# BMS-LV.net
KiCad netlist of a schematic drawn in EAGLE
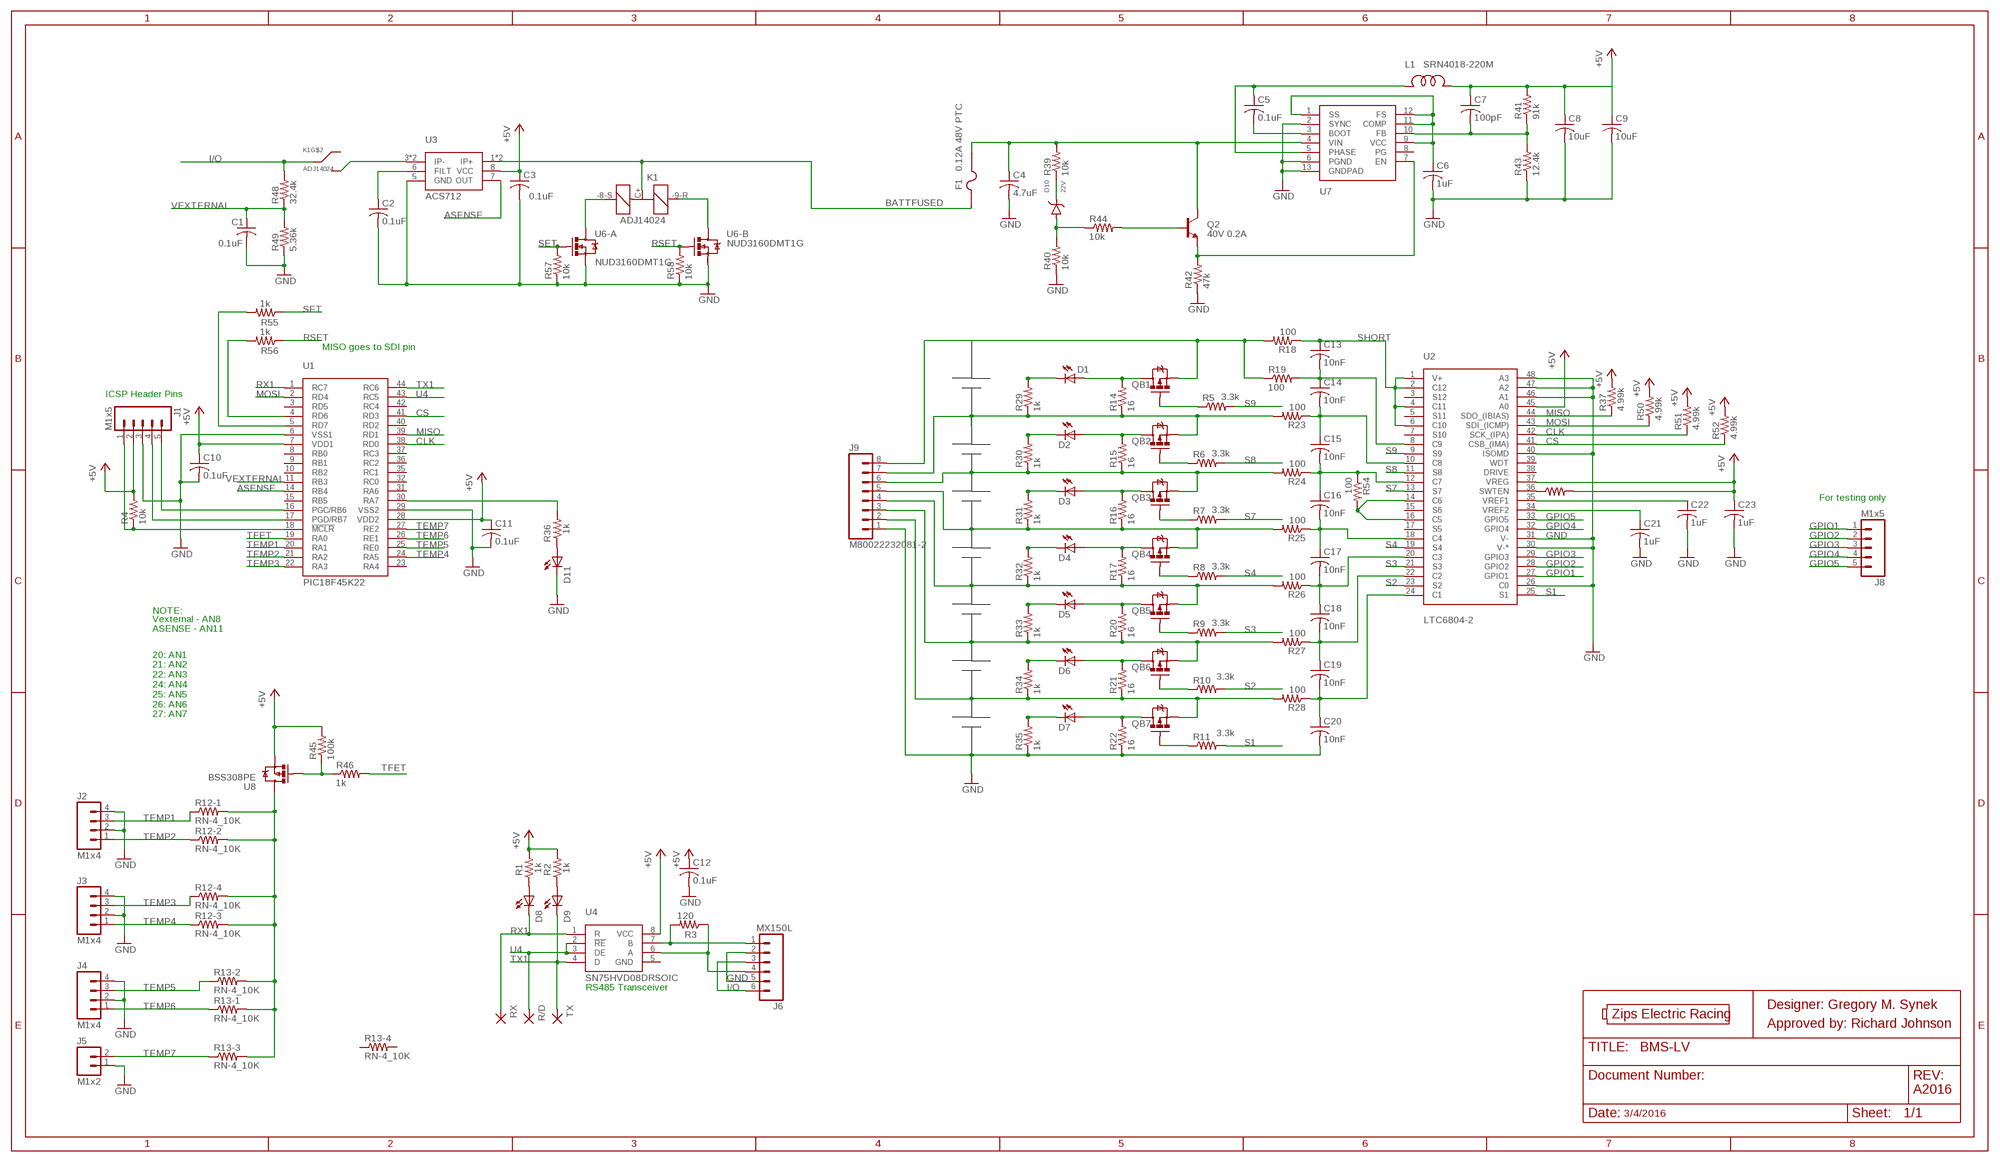
[diagram p0: schematic, sheet 1]

(export (version "E")
  (design (tool "Eeschema 10.0.6"))
  (components
    (comp (ref "C1")
      (value "0.1uF")
      (footprint "eagle-import:0603")
      (fields (field (name "PARTNO") "CC0603ZRY5V9BB104"))
      (libsource (lib "eagle-import") (part "CAP_0.1UF_50V"))
    )
    (comp (ref "C2")
      (value "0.1uF")
      (footprint "eagle-import:0805")
      (fields (field (name "PARTNO") "CL21B104KCC5PNC"))
      (libsource (lib "eagle-import") (part "CAP_0.1UF_100V"))
    )
    (comp (ref "C3")
      (value "0.1uF")
      (footprint "eagle-import:0603")
      (fields (field (name "PARTNO") "CC0603ZRY5V9BB104"))
      (libsource (lib "eagle-import") (part "CAP_0.1UF_50V"))
    )
    (comp (ref "C4")
      (value "4.7uF")
      (footprint "eagle-import:1206@1")
      (fields (field (name "PARTNO") "GRM31CF51H475ZA01L"))
      (libsource (lib "eagle-import") (part "CAP_4.7UF_50V"))
    )
    (comp (ref "C5")
      (value "0.1uF")
      (footprint "eagle-import:0603")
      (fields (field (name "PARTNO") "CC0603ZRY5V9BB104"))
      (libsource (lib "eagle-import") (part "CAP_0.1UF_50V"))
    )
    (comp (ref "C6")
      (value "1uF")
      (footprint "eagle-import:0805")
      (fields (field (name "PARTNO") "UMK212F105ZG-T"))
      (libsource (lib "eagle-import") (part "CAP_1UF_50V_0805"))
    )
    (comp (ref "C7")
      (value "100pF")
      (footprint "eagle-import:0603")
      (fields (field (name "PARTNO") "C1608C0G1H101J080AA"))
      (libsource (lib "eagle-import") (part "CAP_100PF_50V"))
    )
    (comp (ref "C8")
      (value "10uF")
      (footprint "eagle-import:1206@1")
      (fields (field (name "PARTNO") "CL31A106KBHNNNE"))
      (libsource (lib "eagle-import") (part "CAP_10UF_50V"))
    )
    (comp (ref "C9")
      (value "10uF")
      (footprint "eagle-import:1206@1")
      (fields (field (name "PARTNO") "CL31A106KBHNNNE"))
      (libsource (lib "eagle-import") (part "CAP_10UF_50V"))
    )
    (comp (ref "C10")
      (value "0.1uF")
      (footprint "eagle-import:0603")
      (fields (field (name "PARTNO") "CC0603ZRY5V9BB104"))
      (libsource (lib "eagle-import") (part "CAP_0.1UF_50V"))
    )
    (comp (ref "C11")
      (value "0.1uF")
      (footprint "eagle-import:0603")
      (fields (field (name "PARTNO") "CC0603ZRY5V9BB104"))
      (libsource (lib "eagle-import") (part "CAP_0.1UF_50V"))
    )
    (comp (ref "C12")
      (value "0.1uF")
      (footprint "eagle-import:0603")
      (fields (field (name "PARTNO") "CC0603ZRY5V9BB104"))
      (libsource (lib "eagle-import") (part "CAP_0.1UF_50V"))
    )
    (comp (ref "C13")
      (value "10nF")
      (footprint "eagle-import:0603")
      (fields (field (name "PARTNO") "CL10F103ZB8NNNC"))
      (libsource (lib "eagle-import") (part "CAP_10NF_50V"))
    )
    (comp (ref "C14")
      (value "10nF")
      (footprint "eagle-import:0603")
      (fields (field (name "PARTNO") "CL10F103ZB8NNNC"))
      (libsource (lib "eagle-import") (part "CAP_10NF_50V"))
    )
    (comp (ref "C15")
      (value "10nF")
      (footprint "eagle-import:0603")
      (fields (field (name "PARTNO") "CL10F103ZB8NNNC"))
      (libsource (lib "eagle-import") (part "CAP_10NF_50V"))
    )
    (comp (ref "C16")
      (value "10nF")
      (footprint "eagle-import:0603")
      (fields (field (name "PARTNO") "CL10F103ZB8NNNC"))
      (libsource (lib "eagle-import") (part "CAP_10NF_50V"))
    )
    (comp (ref "C17")
      (value "10nF")
      (footprint "eagle-import:0603")
      (fields (field (name "PARTNO") "CL10F103ZB8NNNC"))
      (libsource (lib "eagle-import") (part "CAP_10NF_50V"))
    )
    (comp (ref "C18")
      (value "10nF")
      (footprint "eagle-import:0603")
      (fields (field (name "PARTNO") "CL10F103ZB8NNNC"))
      (libsource (lib "eagle-import") (part "CAP_10NF_50V"))
    )
    (comp (ref "C19")
      (value "10nF")
      (footprint "eagle-import:0603")
      (fields (field (name "PARTNO") "CL10F103ZB8NNNC"))
      (libsource (lib "eagle-import") (part "CAP_10NF_50V"))
    )
    (comp (ref "C20")
      (value "10nF")
      (footprint "eagle-import:0603")
      (fields (field (name "PARTNO") "CL10F103ZB8NNNC"))
      (libsource (lib "eagle-import") (part "CAP_10NF_50V"))
    )
    (comp (ref "C21")
      (value "1uF")
      (footprint "eagle-import:0805")
      (fields (field (name "PARTNO") "UMK212F105ZG-T"))
      (libsource (lib "eagle-import") (part "CAP_1UF_50V_0805"))
    )
    (comp (ref "C22")
      (value "1uF")
      (footprint "eagle-import:0805")
      (fields (field (name "PARTNO") "UMK212F105ZG-T"))
      (libsource (lib "eagle-import") (part "CAP_1UF_50V_0805"))
    )
    (comp (ref "C23")
      (value "1uF")
      (footprint "eagle-import:0805")
      (fields (field (name "PARTNO") "UMK212F105ZG-T"))
      (libsource (lib "eagle-import") (part "CAP_1UF_50V_0805"))
    )
    (comp (ref "D1")
      (value "LED_GREEN")
      (footprint "eagle-import:CHIP_LED0805")
      (fields (field (name "PARTNO") "LTST-S220GKT"))
      (libsource (lib "eagle-import") (part "LED_GREEN"))
    )
    (comp (ref "D2")
      (value "LED_GREEN")
      (footprint "eagle-import:CHIP_LED0805")
      (fields (field (name "PARTNO") "LTST-S220GKT"))
      (libsource (lib "eagle-import") (part "LED_GREEN"))
    )
    (comp (ref "D3")
      (value "LED_GREEN")
      (footprint "eagle-import:CHIP_LED0805")
      (fields (field (name "PARTNO") "LTST-S220GKT"))
      (libsource (lib "eagle-import") (part "LED_GREEN"))
    )
    (comp (ref "D4")
      (value "LED_GREEN")
      (footprint "eagle-import:CHIP_LED0805")
      (fields (field (name "PARTNO") "LTST-S220GKT"))
      (libsource (lib "eagle-import") (part "LED_GREEN"))
    )
    (comp (ref "D5")
      (value "LED_GREEN")
      (footprint "eagle-import:CHIP_LED0805")
      (fields (field (name "PARTNO") "LTST-S220GKT"))
      (libsource (lib "eagle-import") (part "LED_GREEN"))
    )
    (comp (ref "D6")
      (value "LED_GREEN")
      (footprint "eagle-import:CHIP_LED0805")
      (fields (field (name "PARTNO") "LTST-S220GKT"))
      (libsource (lib "eagle-import") (part "LED_GREEN"))
    )
    (comp (ref "D7")
      (value "LED_GREEN")
      (footprint "eagle-import:CHIP_LED0805")
      (fields (field (name "PARTNO") "LTST-S220GKT"))
      (libsource (lib "eagle-import") (part "LED_GREEN"))
    )
    (comp (ref "D8")
      (value "LED_AMBER")
      (footprint "eagle-import:CHIP_LED0805")
      (fields (field (name "PARTNO") "HSMA-C170"))
      (libsource (lib "eagle-import") (part "LED_AMBER"))
    )
    (comp (ref "D9")
      (value "LED_GREEN")
      (footprint "eagle-import:CHIP_LED0805")
      (fields (field (name "PARTNO") "LTST-S220GKT"))
      (libsource (lib "eagle-import") (part "LED_GREEN"))
    )
    (comp (ref "D10")
      (value "22V")
      (footprint "eagle-import:SOD-323")
      (fields (field (name "PARTNO") "MM3Z22VT1G"))
      (libsource (lib "eagle-import") (part "DIODE-ZENER_22V"))
    )
    (comp (ref "D11")
      (value "LED_AMBER")
      (footprint "eagle-import:CHIP_LED0805")
      (fields (field (name "PARTNO") "HSMA-C170"))
      (libsource (lib "eagle-import") (part "LED_AMBER"))
    )
    (comp (ref "F1")
      (value "0.12A 48V PTC")
      (footprint "eagle-import:1206@1")
      (fields (field (name "PARTNO") "0ZCJ0012FF2E"))
      (libsource (lib "eagle-import") (part "FUSE_0.12A_48V_PTC"))
    )
    (comp (ref "J1")
      (value "M1x5")
      (footprint "eagle-import:5X.1")
      (fields (field (name "PARTNO") "GENERIC"))
      (libsource (lib "eagle-import") (part "M5GENERIC"))
    )
    (comp (ref "J2")
      (value "M1x4")
      (footprint "eagle-import:MOLEX_1X4")
      (fields (field (name "PARTNO") "0022232041"))
      (libsource (lib "eagle-import") (part "M4_1X4_LOCK"))
    )
    (comp (ref "J3")
      (value "M1x4")
      (footprint "eagle-import:MOLEX_1X4")
      (fields (field (name "PARTNO") "0022232041"))
      (libsource (lib "eagle-import") (part "M4_1X4_LOCK"))
    )
    (comp (ref "J4")
      (value "M1x4")
      (footprint "eagle-import:MOLEX_1X4")
      (fields (field (name "PARTNO") "0022232041"))
      (libsource (lib "eagle-import") (part "M4_1X4_LOCK"))
    )
    (comp (ref "J5")
      (value "M1x2")
      (footprint "eagle-import:MOLEX-1X2")
      (fields (field (name "PARTNO") "0022232021"))
      (libsource (lib "eagle-import") (part "M2M1X2"))
    )
    (comp (ref "J6")
      (value "MX150L")
      (footprint "eagle-import:MOLEX-MX150L")
      (fields (field (name "PARTNO") "19427-0018"))
      (libsource (lib "eagle-import") (part "M2X3MX150L"))
    )
    (comp (ref "J8")
      (value "M1x5")
      (footprint "eagle-import:5X.1")
      (fields (field (name "PARTNO") "GENERIC"))
      (libsource (lib "eagle-import") (part "M5GENERIC"))
    )
    (comp (ref "J9")
      (value "M80022232081-2")
      (footprint "eagle-import:MOLEX-1X8-2")
      (fields (field (name "PARTNO") "0022232081"))
      (libsource (lib "eagle-import") (part "M80022232081-2"))
    )
    (comp (ref "K1")
      (value "ADJ14024")
      (footprint "eagle-import:ADJ14024")
      (libsource (lib "eagle-import") (part "ADJ14024"))
    )
    (comp (ref "L1")
      (value "SRN4018-220M")
      (footprint "eagle-import:SRN4018")
      (libsource (lib "eagle-import") (part "SRN4018-220M"))
    )
    (comp (ref "Q2")
      (value "40V 0.2A")
      (footprint "eagle-import:SOT23")
      (fields (field (name "PARTNO") "MMBT3904LT1G"))
      (libsource (lib "eagle-import") (part "NPN_40V_0.2A"))
    )
    (comp (ref "QB1")
      (value "MOS-P_DMP2305U-7")
      (footprint "eagle-import:SOT23")
      (fields (field (name "PARTNO") "DMP2305U-7"))
      (libsource (lib "eagle-import") (part "MOS-P_DMP2305U-7"))
    )
    (comp (ref "QB2")
      (value "MOS-P_DMP2305U-7")
      (footprint "eagle-import:SOT23")
      (fields (field (name "PARTNO") "DMP2305U-7"))
      (libsource (lib "eagle-import") (part "MOS-P_DMP2305U-7"))
    )
    (comp (ref "QB3")
      (value "MOS-P_DMP2305U-7")
      (footprint "eagle-import:SOT23")
      (fields (field (name "PARTNO") "DMP2305U-7"))
      (libsource (lib "eagle-import") (part "MOS-P_DMP2305U-7"))
    )
    (comp (ref "QB4")
      (value "MOS-P_DMP2305U-7")
      (footprint "eagle-import:SOT23")
      (fields (field (name "PARTNO") "DMP2305U-7"))
      (libsource (lib "eagle-import") (part "MOS-P_DMP2305U-7"))
    )
    (comp (ref "QB5")
      (value "MOS-P_DMP2305U-7")
      (footprint "eagle-import:SOT23")
      (fields (field (name "PARTNO") "DMP2305U-7"))
      (libsource (lib "eagle-import") (part "MOS-P_DMP2305U-7"))
    )
    (comp (ref "QB6")
      (value "MOS-P_DMP2305U-7")
      (footprint "eagle-import:SOT23")
      (fields (field (name "PARTNO") "DMP2305U-7"))
      (libsource (lib "eagle-import") (part "MOS-P_DMP2305U-7"))
    )
    (comp (ref "QB7")
      (value "MOS-P_DMP2305U-7")
      (footprint "eagle-import:SOT23")
      (fields (field (name "PARTNO") "DMP2305U-7"))
      (libsource (lib "eagle-import") (part "MOS-P_DMP2305U-7"))
    )
    (comp (ref "R/D")
      (value "TPSMD")
      (footprint "eagle-import:0603")
      (fields (field (name "PARTNO") "1625854-3"))
      (libsource (lib "eagle-import") (part "TPSMD"))
    )
    (comp (ref "R1")
      (value "1k")
      (footprint "eagle-import:0603")
      (fields (field (name "PARTNO") "RC0603JR-071KL"))
      (libsource (lib "eagle-import") (part "RES_1K_5%"))
    )
    (comp (ref "R2")
      (value "1k")
      (footprint "eagle-import:0603")
      (fields (field (name "PARTNO") "RC0603JR-071KL"))
      (libsource (lib "eagle-import") (part "RES_1K_5%"))
    )
    (comp (ref "R3")
      (value "120")
      (footprint "eagle-import:0603")
      (fields (field (name "PARTNO") "RC0603FR-07120RL"))
      (libsource (lib "eagle-import") (part "RES_120_1%"))
    )
    (comp (ref "R4")
      (value "10k")
      (footprint "eagle-import:0603")
      (fields (field (name "PARTNO") "RC0603FR-0710KL"))
      (libsource (lib "eagle-import") (part "RES_10K_1%"))
    )
    (comp (ref "R5")
      (value "3.3k")
      (footprint "eagle-import:0805")
      (fields (field (name "PARTNO") "RC0805FR-073K3L"))
      (libsource (lib "eagle-import") (part "RES_3.3K_1%_0805"))
    )
    (comp (ref "R6")
      (value "3.3k")
      (footprint "eagle-import:0805")
      (fields (field (name "PARTNO") "RC0805FR-073K3L"))
      (libsource (lib "eagle-import") (part "RES_3.3K_1%_0805"))
    )
    (comp (ref "R7")
      (value "3.3k")
      (footprint "eagle-import:0805")
      (fields (field (name "PARTNO") "RC0805FR-073K3L"))
      (libsource (lib "eagle-import") (part "RES_3.3K_1%_0805"))
    )
    (comp (ref "R8")
      (value "3.3k")
      (footprint "eagle-import:0805")
      (fields (field (name "PARTNO") "RC0805FR-073K3L"))
      (libsource (lib "eagle-import") (part "RES_3.3K_1%_0805"))
    )
    (comp (ref "R9")
      (value "3.3k")
      (footprint "eagle-import:0805")
      (fields (field (name "PARTNO") "RC0805FR-073K3L"))
      (libsource (lib "eagle-import") (part "RES_3.3K_1%_0805"))
    )
    (comp (ref "R10")
      (value "3.3k")
      (footprint "eagle-import:0805")
      (fields (field (name "PARTNO") "RC0805FR-073K3L"))
      (libsource (lib "eagle-import") (part "RES_3.3K_1%_0805"))
    )
    (comp (ref "R11")
      (value "3.3k")
      (footprint "eagle-import:0805")
      (fields (field (name "PARTNO") "RC0805FR-073K3L"))
      (libsource (lib "eagle-import") (part "RES_3.3K_1%_0805"))
    )
    (comp (ref "R12")
      (value "RN-4_10K")
      (footprint "eagle-import:MNR14")
      (fields (field (name "PARTNO") "MNR14ERAPJ103"))
      (libsource (lib "eagle-import") (part "RN-4_10K"))
    )
    (comp (ref "R13")
      (value "RN-4_10K")
      (footprint "eagle-import:MNR14")
      (fields (field (name "PARTNO") "MNR14ERAPJ103"))
      (libsource (lib "eagle-import") (part "RN-4_10K"))
    )
    (comp (ref "R14")
      (value "16")
      (footprint "eagle-import:RR02J16RTB")
      (fields (field (name "PARTNO") "RR02J16RTB"))
      (libsource (lib "eagle-import") (part "RES_16_5%_TH"))
    )
    (comp (ref "R15")
      (value "16")
      (footprint "eagle-import:RR02J16RTB")
      (fields (field (name "PARTNO") "RR02J16RTB"))
      (libsource (lib "eagle-import") (part "RES_16_5%_TH"))
    )
    (comp (ref "R16")
      (value "16")
      (footprint "eagle-import:RR02J16RTB")
      (fields (field (name "PARTNO") "RR02J16RTB"))
      (libsource (lib "eagle-import") (part "RES_16_5%_TH"))
    )
    (comp (ref "R17")
      (value "16")
      (footprint "eagle-import:RR02J16RTB")
      (fields (field (name "PARTNO") "RR02J16RTB"))
      (libsource (lib "eagle-import") (part "RES_16_5%_TH"))
    )
    (comp (ref "R18")
      (value "100")
      (footprint "eagle-import:0603")
      (fields (field (name "PARTNO") "RC0603FR-07100RL"))
      (libsource (lib "eagle-import") (part "RES_100_1%"))
    )
    (comp (ref "R19")
      (value "100")
      (footprint "eagle-import:0603")
      (fields (field (name "PARTNO") "RC0603FR-07100RL"))
      (libsource (lib "eagle-import") (part "RES_100_1%"))
    )
    (comp (ref "R20")
      (value "16")
      (footprint "eagle-import:RR02J16RTB")
      (fields (field (name "PARTNO") "RR02J16RTB"))
      (libsource (lib "eagle-import") (part "RES_16_5%_TH"))
    )
    (comp (ref "R21")
      (value "16")
      (footprint "eagle-import:RR02J16RTB")
      (fields (field (name "PARTNO") "RR02J16RTB"))
      (libsource (lib "eagle-import") (part "RES_16_5%_TH"))
    )
    (comp (ref "R22")
      (value "16")
      (footprint "eagle-import:RR02J16RTB")
      (fields (field (name "PARTNO") "RR02J16RTB"))
      (libsource (lib "eagle-import") (part "RES_16_5%_TH"))
    )
    (comp (ref "R23")
      (value "100")
      (footprint "eagle-import:0603")
      (fields (field (name "PARTNO") "RC0603FR-07100RL"))
      (libsource (lib "eagle-import") (part "RES_100_1%"))
    )
    (comp (ref "R24")
      (value "100")
      (footprint "eagle-import:0603")
      (fields (field (name "PARTNO") "RC0603FR-07100RL"))
      (libsource (lib "eagle-import") (part "RES_100_1%"))
    )
    (comp (ref "R25")
      (value "100")
      (footprint "eagle-import:0603")
      (fields (field (name "PARTNO") "RC0603FR-07100RL"))
      (libsource (lib "eagle-import") (part "RES_100_1%"))
    )
    (comp (ref "R26")
      (value "100")
      (footprint "eagle-import:0603")
      (fields (field (name "PARTNO") "RC0603FR-07100RL"))
      (libsource (lib "eagle-import") (part "RES_100_1%"))
    )
    (comp (ref "R27")
      (value "100")
      (footprint "eagle-import:0603")
      (fields (field (name "PARTNO") "RC0603FR-07100RL"))
      (libsource (lib "eagle-import") (part "RES_100_1%"))
    )
    (comp (ref "R28")
      (value "100")
      (footprint "eagle-import:0603")
      (fields (field (name "PARTNO") "RC0603FR-07100RL"))
      (libsource (lib "eagle-import") (part "RES_100_1%"))
    )
    (comp (ref "R29")
      (value "1k")
      (footprint "eagle-import:0603")
      (fields (field (name "PARTNO") "RC0603JR-071KL"))
      (libsource (lib "eagle-import") (part "RES_1K_5%"))
    )
    (comp (ref "R30")
      (value "1k")
      (footprint "eagle-import:0603")
      (fields (field (name "PARTNO") "RC0603JR-071KL"))
      (libsource (lib "eagle-import") (part "RES_1K_5%"))
    )
    (comp (ref "R31")
      (value "1k")
      (footprint "eagle-import:0603")
      (fields (field (name "PARTNO") "RC0603JR-071KL"))
      (libsource (lib "eagle-import") (part "RES_1K_5%"))
    )
    (comp (ref "R32")
      (value "1k")
      (footprint "eagle-import:0603")
      (fields (field (name "PARTNO") "RC0603JR-071KL"))
      (libsource (lib "eagle-import") (part "RES_1K_5%"))
    )
    (comp (ref "R33")
      (value "1k")
      (footprint "eagle-import:0603")
      (fields (field (name "PARTNO") "RC0603JR-071KL"))
      (libsource (lib "eagle-import") (part "RES_1K_5%"))
    )
    (comp (ref "R34")
      (value "1k")
      (footprint "eagle-import:0603")
      (fields (field (name "PARTNO") "RC0603JR-071KL"))
      (libsource (lib "eagle-import") (part "RES_1K_5%"))
    )
    (comp (ref "R35")
      (value "1k")
      (footprint "eagle-import:0603")
      (fields (field (name "PARTNO") "RC0603JR-071KL"))
      (libsource (lib "eagle-import") (part "RES_1K_5%"))
    )
    (comp (ref "R36")
      (value "1k")
      (footprint "eagle-import:0603")
      (fields (field (name "PARTNO") "RC0603JR-071KL"))
      (libsource (lib "eagle-import") (part "RES_1K_5%"))
    )
    (comp (ref "R37")
      (value "4.99k")
      (footprint "eagle-import:0603")
      (fields (field (name "PARTNO") "ERJ-3EKF4991V"))
      (libsource (lib "eagle-import") (part "RES_4.99K_1%"))
    )
    (comp (ref "R39")
      (value "10k")
      (footprint "eagle-import:0603")
      (fields (field (name "PARTNO") "RC0603FR-0710KL"))
      (libsource (lib "eagle-import") (part "RES_10K_1%"))
    )
    (comp (ref "R40")
      (value "10k")
      (footprint "eagle-import:0603")
      (fields (field (name "PARTNO") "RC0603FR-0710KL"))
      (libsource (lib "eagle-import") (part "RES_10K_1%"))
    )
    (comp (ref "R41")
      (value "91k")
      (footprint "eagle-import:0805")
      (fields (field (name "PARTNO") "ERJ-6ENF9102V"))
      (libsource (lib "eagle-import") (part "RES_91K_1%_0805"))
    )
    (comp (ref "R42")
      (value "47k")
      (footprint "eagle-import:0603")
      (fields (field (name "PARTNO") "RC0603FR-0747KL"))
      (libsource (lib "eagle-import") (part "RES_47K_1%"))
    )
    (comp (ref "R43")
      (value "12.4k")
      (footprint "eagle-import:0603")
      (fields (field (name "PARTNO") "RC0603FR-0712K4L"))
      (libsource (lib "eagle-import") (part "RES_12.4K_1%"))
    )
    (comp (ref "R44")
      (value "10k")
      (footprint "eagle-import:0603")
      (fields (field (name "PARTNO") "RC0603FR-0710KL"))
      (libsource (lib "eagle-import") (part "RES_10K_1%"))
    )
    (comp (ref "R45")
      (value "100k")
      (footprint "eagle-import:0805")
      (fields (field (name "PARTNO") "RC0805FR-07100KL"))
      (libsource (lib "eagle-import") (part "RES_100K_1%_0805"))
    )
    (comp (ref "R46")
      (value "1k")
      (footprint "eagle-import:0805")
      (fields (field (name "PARTNO") "RC0805FR-071KL"))
      (libsource (lib "eagle-import") (part "RES_1K_1%_0805"))
    )
    (comp (ref "R47")
      (value "RES_0_1%")
      (footprint "eagle-import:0603")
      (fields (field (name "PARTNO") "CRCW06030000Z0EA"))
      (libsource (lib "eagle-import") (part "RES_0_1%"))
    )
    (comp (ref "R48")
      (value "32.4k")
      (footprint "eagle-import:0603")
      (fields (field (name "PARTNO") "RC0603FR-0732K4L"))
      (libsource (lib "eagle-import") (part "RES_32.4K_1%"))
    )
    (comp (ref "R49")
      (value "5.36k")
      (footprint "eagle-import:0603")
      (fields (field (name "PARTNO") "RC0603FR-075K36L"))
      (libsource (lib "eagle-import") (part "RES_5.36K_1%"))
    )
    (comp (ref "R50")
      (value "4.99k")
      (footprint "eagle-import:0603")
      (fields (field (name "PARTNO") "ERJ-3EKF4991V"))
      (libsource (lib "eagle-import") (part "RES_4.99K_1%"))
    )
    (comp (ref "R51")
      (value "4.99k")
      (footprint "eagle-import:0603")
      (fields (field (name "PARTNO") "ERJ-3EKF4991V"))
      (libsource (lib "eagle-import") (part "RES_4.99K_1%"))
    )
    (comp (ref "R52")
      (value "4.99k")
      (footprint "eagle-import:0603")
      (fields (field (name "PARTNO") "ERJ-3EKF4991V"))
      (libsource (lib "eagle-import") (part "RES_4.99K_1%"))
    )
    (comp (ref "R54")
      (value "100")
      (footprint "eagle-import:0805")
      (fields (field (name "PARTNO") "RC0805FR-071KL"))
      (libsource (lib "eagle-import") (part "RES_1K_1%_0805"))
    )
    (comp (ref "R55")
      (value "1k")
      (footprint "eagle-import:0603")
      (fields (field (name "PARTNO") "RC0603JR-071KL"))
      (libsource (lib "eagle-import") (part "RES_1K_5%"))
    )
    (comp (ref "R56")
      (value "1k")
      (footprint "eagle-import:0603")
      (fields (field (name "PARTNO") "RC0603JR-071KL"))
      (libsource (lib "eagle-import") (part "RES_1K_5%"))
    )
    (comp (ref "R57")
      (value "10k")
      (footprint "eagle-import:0603")
      (fields (field (name "PARTNO") "RC0603FR-0710KL"))
      (libsource (lib "eagle-import") (part "RES_10K_1%"))
    )
    (comp (ref "R58")
      (value "10k")
      (footprint "eagle-import:0603")
      (fields (field (name "PARTNO") "RC0603FR-0710KL"))
      (libsource (lib "eagle-import") (part "RES_10K_1%"))
    )
    (comp (ref "RX")
      (value "TPSMD")
      (footprint "eagle-import:0603")
      (fields (field (name "PARTNO") "1625854-3"))
      (libsource (lib "eagle-import") (part "TPSMD"))
    )
    (comp (ref "TX")
      (value "TPSMD")
      (footprint "eagle-import:0603")
      (fields (field (name "PARTNO") "1625854-3"))
      (libsource (lib "eagle-import") (part "TPSMD"))
    )
    (comp (ref "U1")
      (value "PIC18F45K22")
      (footprint "eagle-import:TQFP-44")
      (fields (field (name "PARTNO") "PIC18F45K22T-I/PT"))
      (libsource (lib "eagle-import") (part "PIC18F45K22"))
    )
    (comp (ref "U2")
      (value "LTC6804-2")
      (footprint "eagle-import:SSOP-48")
      (fields (field (name "PARTNO") "LTC6804IG-2#PBF"))
      (libsource (lib "eagle-import") (part "LTC6804-2"))
    )
    (comp (ref "U3")
      (value "ACS712")
      (footprint "eagle-import:SO-8")
      (fields (field (name "PARTNO") "ACS712ELCTR-30A-T"))
      (libsource (lib "eagle-import") (part "ACS712ELCTR-30A-T"))
    )
    (comp (ref "U4")
      (value "SN75HVD08DRSOIC")
      (footprint "eagle-import:SO-8")
      (fields (field (name "PARTNO") "SN75HVD08DR"))
      (libsource (lib "eagle-import") (part "SN75HVD08DRSOIC"))
    )
    (comp (ref "U6")
      (value "NUD3160DMT1G")
      (footprint "eagle-import:SC74-6")
      (libsource (lib "eagle-import") (part "NUD3160DMT1G"))
    )
    (comp (ref "U7")
      (value "ISL85415-FRZ-T7A")
      (footprint "eagle-import:DFN-12")
      (fields (field (name "PARTNO") "ISL85415FRZ-T7A"))
      (libsource (lib "eagle-import") (part "ISL85415-FRZ-T7A"))
    )
    (comp (ref "U8")
      (value "BSS308PE")
      (footprint "eagle-import:SOT23")
      (fields (field (name "PARTNO") "BSS308PE H6327"))
      (libsource (lib "eagle-import") (part "BSS308PEBSS308PE"))
    )
  )
  (nets
    (net (code "1") (name "+5V") (class "Default")
      (node (ref "C10") (pin "1") (pinfunction "+_1") (pintype "passive"))
      (node (ref "C11") (pin "1") (pinfunction "+_1") (pintype "passive"))
      (node (ref "C12") (pin "1") (pinfunction "+_1") (pintype "passive"))
      (node (ref "C23") (pin "1") (pinfunction "+_1") (pintype "passive"))
      (node (ref "C3") (pin "1") (pinfunction "+_1") (pintype "passive"))
      (node (ref "C7") (pin "1") (pinfunction "+_1") (pintype "passive"))
      (node (ref "C8") (pin "1") (pinfunction "+_1") (pintype "passive"))
      (node (ref "C9") (pin "1") (pinfunction "+_1") (pintype "passive"))
      (node (ref "J1") (pin "2") (pinfunction "2_2") (pintype "passive"))
      (node (ref "L1") (pin "P$2") (pinfunction "P$2_P$2") (pintype "bidirectional"))
      (node (ref "R1") (pin "2") (pinfunction "2_2") (pintype "passive"))
      (node (ref "R2") (pin "2") (pinfunction "2_2") (pintype "passive"))
      (node (ref "R37") (pin "2") (pinfunction "2_2") (pintype "passive"))
      (node (ref "R4") (pin "2") (pinfunction "2_2") (pintype "passive"))
      (node (ref "R41") (pin "2") (pinfunction "2_2") (pintype "passive"))
      (node (ref "R45") (pin "2") (pinfunction "2_2") (pintype "passive"))
      (node (ref "R47") (pin "2") (pinfunction "2_2") (pintype "passive"))
      (node (ref "R50") (pin "2") (pinfunction "2_2") (pintype "passive"))
      (node (ref "R51") (pin "2") (pinfunction "2_2") (pintype "passive"))
      (node (ref "R52") (pin "2") (pinfunction "2_2") (pintype "passive"))
      (node (ref "U1") (pin "28") (pinfunction "VDD2_28") (pintype "bidirectional"))
      (node (ref "U1") (pin "7") (pinfunction "VDD1_7") (pintype "bidirectional"))
      (node (ref "U2") (pin "37") (pinfunction "VREG_37") (pintype "bidirectional"))
      (node (ref "U2") (pin "45") (pinfunction "A0_45") (pintype "bidirectional"))
      (node (ref "U3") (pin "8") (pinfunction "VCC_8") (pintype "bidirectional"))
      (node (ref "U4") (pin "8") (pinfunction "VCC_8") (pintype "bidirectional"))
      (node (ref "U8") (pin "3") (pinfunction "S_3") (pintype "passive"))
    )
    (net (code "2") (name "/ASENSE") (class "Default")
      (node (ref "U1") (pin "14") (pinfunction "RB4_14") (pintype "bidirectional"))
      (node (ref "U3") (pin "7") (pinfunction "OUT_7") (pintype "bidirectional"))
    )
    (net (code "3") (name "/BATTFUSED") (class "Default")
      (node (ref "F1") (pin "1") (pinfunction "P$1_1") (pintype "bidirectional"))
      (node (ref "K1") (pin "C+") (pinfunction "-_C+") (pintype "passive"))
      (node (ref "U3") (pin "1") (pinfunction "IP+_1") (pintype "bidirectional"))
      (node (ref "U3") (pin "2") (pinfunction "IP+_2") (pintype "bidirectional"))
    )
    (net (code "4") (name "/CLK") (class "Default")
      (node (ref "R51") (pin "1") (pinfunction "1_1") (pintype "passive"))
      (node (ref "U1") (pin "38") (pinfunction "RD0_38") (pintype "bidirectional"))
      (node (ref "U2") (pin "42") (pinfunction "SCK_(IPA)_42") (pintype "bidirectional"))
    )
    (net (code "5") (name "/CS") (class "Default")
      (node (ref "R52") (pin "1") (pinfunction "1_1") (pintype "passive"))
      (node (ref "U1") (pin "41") (pinfunction "RD3_41") (pintype "bidirectional"))
      (node (ref "U2") (pin "41") (pinfunction "CSB_(IMA)_41") (pintype "bidirectional"))
    )
    (net (code "6") (name "/GPIO1") (class "Default")
      (node (ref "J8") (pin "1") (pinfunction "1_1") (pintype "passive"))
      (node (ref "U2") (pin "27") (pinfunction "GPIO1_27") (pintype "bidirectional"))
    )
    (net (code "7") (name "/GPIO2") (class "Default")
      (node (ref "J8") (pin "2") (pinfunction "2_2") (pintype "passive"))
      (node (ref "U2") (pin "28") (pinfunction "GPIO2_28") (pintype "bidirectional"))
    )
    (net (code "8") (name "/GPIO3") (class "Default")
      (node (ref "J8") (pin "3") (pinfunction "3_3") (pintype "passive"))
      (node (ref "U2") (pin "29") (pinfunction "GPIO3_29") (pintype "bidirectional"))
    )
    (net (code "9") (name "/GPIO4") (class "Default")
      (node (ref "J8") (pin "4") (pinfunction "4_4") (pintype "passive"))
      (node (ref "U2") (pin "32") (pinfunction "GPIO4_32") (pintype "bidirectional"))
    )
    (net (code "10") (name "/GPIO5") (class "Default")
      (node (ref "J8") (pin "5") (pinfunction "5_5") (pintype "passive"))
      (node (ref "U2") (pin "33") (pinfunction "GPIO5_33") (pintype "bidirectional"))
    )
    (net (code "11") (name "/I{slash}O") (class "Default")
      (node (ref "J6") (pin "3") (pinfunction "3_3") (pintype "passive"))
      (node (ref "J6") (pin "6") (pinfunction "6_6") (pintype "passive"))
      (node (ref "K1") (pin "C") (pinfunction "C_C") (pintype "bidirectional"))
      (node (ref "R48") (pin "2") (pinfunction "2_2") (pintype "passive"))
    )
    (net (code "12") (name "/MISO") (class "Default")
      (node (ref "R37") (pin "1") (pinfunction "1_1") (pintype "passive"))
      (node (ref "U1") (pin "39") (pinfunction "RD1_39") (pintype "bidirectional"))
      (node (ref "U2") (pin "44") (pinfunction "SDO_(IBIAS)_44") (pintype "bidirectional"))
    )
    (net (code "13") (name "/MOSI") (class "Default")
      (node (ref "R50") (pin "1") (pinfunction "1_1") (pintype "passive"))
      (node (ref "U1") (pin "2") (pinfunction "RD4_2") (pintype "bidirectional"))
      (node (ref "U2") (pin "43") (pinfunction "SDI_(ICMP)_43") (pintype "bidirectional"))
    )
    (net (code "14") (name "/RSET") (class "Default")
      (node (ref "R56") (pin "1") (pinfunction "1_1") (pintype "passive"))
      (node (ref "R58") (pin "2") (pinfunction "2_2") (pintype "passive"))
      (node (ref "U6") (pin "5") (pinfunction "G_5") (pintype "passive"))
    )
    (net (code "15") (name "/RX1") (class "Default")
      (node (ref "D8") (pin "C") (pinfunction "C_C") (pintype "passive"))
      (node (ref "RX") (pin "1") (pinfunction "P$1_1") (pintype "bidirectional"))
      (node (ref "RX") (pin "2") (pinfunction "P$1_2") (pintype "bidirectional"))
      (node (ref "U1") (pin "1") (pinfunction "RC7_1") (pintype "bidirectional"))
      (node (ref "U4") (pin "1") (pinfunction "R_1") (pintype "bidirectional"))
    )
    (net (code "16") (name "/S1") (class "Default")
      (node (ref "R11") (pin "2") (pinfunction "2_2") (pintype "passive"))
      (node (ref "U2") (pin "25") (pinfunction "S1_25") (pintype "bidirectional"))
    )
    (net (code "17") (name "/S2") (class "Default")
      (node (ref "R10") (pin "2") (pinfunction "2_2") (pintype "passive"))
      (node (ref "U2") (pin "23") (pinfunction "S2_23") (pintype "bidirectional"))
    )
    (net (code "18") (name "/S3") (class "Default")
      (node (ref "R9") (pin "2") (pinfunction "2_2") (pintype "passive"))
      (node (ref "U2") (pin "21") (pinfunction "S3_21") (pintype "bidirectional"))
    )
    (net (code "19") (name "/S4") (class "Default")
      (node (ref "R8") (pin "2") (pinfunction "2_2") (pintype "passive"))
      (node (ref "U2") (pin "19") (pinfunction "S4_19") (pintype "bidirectional"))
    )
    (net (code "20") (name "/S7") (class "Default")
      (node (ref "R7") (pin "2") (pinfunction "2_2") (pintype "passive"))
      (node (ref "U2") (pin "13") (pinfunction "S7_13") (pintype "bidirectional"))
    )
    (net (code "21") (name "/S8") (class "Default")
      (node (ref "R6") (pin "2") (pinfunction "2_2") (pintype "passive"))
      (node (ref "U2") (pin "11") (pinfunction "S8_11") (pintype "bidirectional"))
    )
    (net (code "22") (name "/S9") (class "Default")
      (node (ref "R5") (pin "2") (pinfunction "2_2") (pintype "passive"))
      (node (ref "U2") (pin "9") (pinfunction "S9_9") (pintype "bidirectional"))
    )
    (net (code "23") (name "/SET") (class "Default")
      (node (ref "R55") (pin "1") (pinfunction "1_1") (pintype "passive"))
      (node (ref "R57") (pin "2") (pinfunction "2_2") (pintype "passive"))
      (node (ref "U6") (pin "2") (pinfunction "G_2") (pintype "passive"))
    )
    (net (code "24") (name "/SHORT") (class "Default")
      (node (ref "C13") (pin "1") (pinfunction "+_1") (pintype "passive"))
      (node (ref "R18") (pin "1") (pinfunction "1_1") (pintype "passive"))
      (node (ref "U2") (pin "1") (pinfunction "V+_1") (pintype "bidirectional"))
      (node (ref "U2") (pin "2") (pinfunction "C12_2") (pintype "bidirectional"))
      (node (ref "U2") (pin "4") (pinfunction "C11_4") (pintype "bidirectional"))
      (node (ref "U2") (pin "6") (pinfunction "C10_6") (pintype "bidirectional"))
    )
    (net (code "25") (name "/TEMP1") (class "Default")
      (node (ref "J2") (pin "3") (pinfunction "3_3") (pintype "passive"))
      (node (ref "R12") (pin "1") (pinfunction "1_1") (pintype "passive"))
      (node (ref "U1") (pin "20") (pinfunction "RA1_20") (pintype "bidirectional"))
    )
    (net (code "26") (name "/TEMP2") (class "Default")
      (node (ref "J2") (pin "1") (pinfunction "1_1") (pintype "passive"))
      (node (ref "R12") (pin "2") (pinfunction "1_2") (pintype "passive"))
      (node (ref "U1") (pin "21") (pinfunction "RA2_21") (pintype "bidirectional"))
    )
    (net (code "27") (name "/TEMP3") (class "Default")
      (node (ref "J3") (pin "3") (pinfunction "3_3") (pintype "passive"))
      (node (ref "R12") (pin "4") (pinfunction "1_4") (pintype "passive"))
      (node (ref "U1") (pin "22") (pinfunction "RA3_22") (pintype "bidirectional"))
    )
    (net (code "28") (name "/TEMP4") (class "Default")
      (node (ref "J3") (pin "1") (pinfunction "1_1") (pintype "passive"))
      (node (ref "R12") (pin "3") (pinfunction "1_3") (pintype "passive"))
      (node (ref "U1") (pin "24") (pinfunction "RA5_24") (pintype "bidirectional"))
    )
    (net (code "29") (name "/TEMP5") (class "Default")
      (node (ref "J4") (pin "3") (pinfunction "3_3") (pintype "passive"))
      (node (ref "R13") (pin "2") (pinfunction "1_2") (pintype "passive"))
      (node (ref "U1") (pin "25") (pinfunction "RE0_25") (pintype "bidirectional"))
    )
    (net (code "30") (name "/TEMP6") (class "Default")
      (node (ref "J4") (pin "1") (pinfunction "1_1") (pintype "passive"))
      (node (ref "R13") (pin "1") (pinfunction "1_1") (pintype "passive"))
      (node (ref "U1") (pin "26") (pinfunction "RE1_26") (pintype "bidirectional"))
    )
    (net (code "31") (name "/TEMP7") (class "Default")
      (node (ref "J5") (pin "2") (pinfunction "2_2") (pintype "passive"))
      (node (ref "R13") (pin "3") (pinfunction "1_3") (pintype "passive"))
      (node (ref "U1") (pin "27") (pinfunction "RE2_27") (pintype "bidirectional"))
    )
    (net (code "32") (name "/TFET") (class "Default")
      (node (ref "R46") (pin "2") (pinfunction "2_2") (pintype "passive"))
      (node (ref "U1") (pin "19") (pinfunction "RA0_19") (pintype "bidirectional"))
    )
    (net (code "33") (name "/TX1") (class "Default")
      (node (ref "D9") (pin "C") (pinfunction "C_C") (pintype "passive"))
      (node (ref "TX") (pin "1") (pinfunction "P$1_1") (pintype "bidirectional"))
      (node (ref "TX") (pin "2") (pinfunction "P$1_2") (pintype "bidirectional"))
      (node (ref "U1") (pin "44") (pinfunction "RC6_44") (pintype "bidirectional"))
      (node (ref "U4") (pin "4") (pinfunction "D_4") (pintype "bidirectional"))
    )
    (net (code "34") (name "/U4") (class "Default")
      (node (ref "R/D") (pin "1") (pinfunction "P$1_1") (pintype "bidirectional"))
      (node (ref "R/D") (pin "2") (pinfunction "P$1_2") (pintype "bidirectional"))
      (node (ref "U1") (pin "43") (pinfunction "RC5_43") (pintype "bidirectional"))
      (node (ref "U4") (pin "2") (pinfunction "~{RE}_2") (pintype "bidirectional"))
      (node (ref "U4") (pin "3") (pinfunction "DE_3") (pintype "bidirectional"))
    )
    (net (code "35") (name "/VEXTERNAL") (class "Default")
      (node (ref "C1") (pin "1") (pinfunction "+_1") (pintype "passive"))
      (node (ref "R48") (pin "1") (pinfunction "1_1") (pintype "passive"))
      (node (ref "R49") (pin "2") (pinfunction "2_2") (pintype "passive"))
      (node (ref "U1") (pin "11") (pinfunction "RB3_11") (pintype "bidirectional"))
    )
    (net (code "36") (name "GND") (class "Default")
      (node (ref "C1") (pin "2") (pinfunction "-_2") (pintype "passive"))
      (node (ref "C10") (pin "2") (pinfunction "-_2") (pintype "passive"))
      (node (ref "C11") (pin "2") (pinfunction "-_2") (pintype "passive"))
      (node (ref "C12") (pin "2") (pinfunction "-_2") (pintype "passive"))
      (node (ref "C2") (pin "2") (pinfunction "-_2") (pintype "passive"))
      (node (ref "C20") (pin "2") (pinfunction "-_2") (pintype "passive"))
      (node (ref "C21") (pin "2") (pinfunction "-_2") (pintype "passive"))
      (node (ref "C22") (pin "2") (pinfunction "-_2") (pintype "passive"))
      (node (ref "C23") (pin "2") (pinfunction "-_2") (pintype "passive"))
      (node (ref "C3") (pin "2") (pinfunction "-_2") (pintype "passive"))
      (node (ref "C4") (pin "2") (pinfunction "-_2") (pintype "passive"))
      (node (ref "C6") (pin "2") (pinfunction "-_2") (pintype "passive"))
      (node (ref "C8") (pin "2") (pinfunction "-_2") (pintype "passive"))
      (node (ref "C9") (pin "2") (pinfunction "-_2") (pintype "passive"))
      (node (ref "D11") (pin "C") (pinfunction "C_C") (pintype "passive"))
      (node (ref "J1") (pin "3") (pinfunction "3_3") (pintype "passive"))
      (node (ref "J2") (pin "2") (pinfunction "2_2") (pintype "passive"))
      (node (ref "J2") (pin "4") (pinfunction "4_4") (pintype "passive"))
      (node (ref "J3") (pin "2") (pinfunction "2_2") (pintype "passive"))
      (node (ref "J3") (pin "4") (pinfunction "4_4") (pintype "passive"))
      (node (ref "J4") (pin "2") (pinfunction "2_2") (pintype "passive"))
      (node (ref "J4") (pin "4") (pinfunction "4_4") (pintype "passive"))
      (node (ref "J5") (pin "1") (pinfunction "1_1") (pintype "passive"))
      (node (ref "J6") (pin "2") (pinfunction "2_2") (pintype "passive"))
      (node (ref "J6") (pin "5") (pinfunction "5_5") (pintype "passive"))
      (node (ref "J9") (pin "1") (pinfunction "1_1") (pintype "passive"))
      (node (ref "R22") (pin "P$1") (pinfunction "1_P$1") (pintype "passive"))
      (node (ref "R35") (pin "1") (pinfunction "1_1") (pintype "passive"))
      (node (ref "R40") (pin "1") (pinfunction "1_1") (pintype "passive"))
      (node (ref "R42") (pin "1") (pinfunction "1_1") (pintype "passive"))
      (node (ref "R43") (pin "1") (pinfunction "1_1") (pintype "passive"))
      (node (ref "R49") (pin "1") (pinfunction "1_1") (pintype "passive"))
      (node (ref "R57") (pin "1") (pinfunction "1_1") (pintype "passive"))
      (node (ref "R58") (pin "1") (pinfunction "1_1") (pintype "passive"))
      (node (ref "U1") (pin "29") (pinfunction "VSS2_29") (pintype "bidirectional"))
      (node (ref "U1") (pin "6") (pinfunction "VSS1_6") (pintype "bidirectional"))
      (node (ref "U2") (pin "26") (pinfunction "C0_26") (pintype "bidirectional"))
      (node (ref "U2") (pin "30") (pinfunction "V-*_30") (pintype "bidirectional"))
      (node (ref "U2") (pin "31") (pinfunction "V-_31") (pintype "bidirectional"))
      (node (ref "U2") (pin "40") (pinfunction "ISOMD_40") (pintype "bidirectional"))
      (node (ref "U2") (pin "46") (pinfunction "A1_46") (pintype "bidirectional"))
      (node (ref "U2") (pin "47") (pinfunction "A2_47") (pintype "bidirectional"))
      (node (ref "U2") (pin "48") (pinfunction "A3_48") (pintype "bidirectional"))
      (node (ref "U3") (pin "5") (pinfunction "GND_5") (pintype "bidirectional"))
      (node (ref "U6") (pin "1") (pinfunction "S_1") (pintype "passive"))
      (node (ref "U6") (pin "4") (pinfunction "S_4") (pintype "passive"))
      (node (ref "U7") (pin "13") (pinfunction "GNDPAD_13") (pintype "bidirectional"))
      (node (ref "U7") (pin "2") (pinfunction "SYNC_2") (pintype "bidirectional"))
      (node (ref "U7") (pin "6") (pinfunction "PGND_6") (pintype "bidirectional"))
    )
    (net (code "37") (name "Net-(C2-+)") (class "Default")
      (node (ref "C2") (pin "1") (pinfunction "+_1") (pintype "passive"))
      (node (ref "U3") (pin "6") (pinfunction "FILT_6") (pintype "bidirectional"))
    )
    (net (code "38") (name "Net-(C4-+)") (class "Default")
      (node (ref "C4") (pin "1") (pinfunction "+_1") (pintype "passive"))
      (node (ref "F1") (pin "2") (pinfunction "P$2_2") (pintype "bidirectional"))
      (node (ref "Q2") (pin "3") (pinfunction "P$3_3") (pintype "input"))
      (node (ref "R39") (pin "2") (pinfunction "2_2") (pintype "passive"))
      (node (ref "U7") (pin "4") (pinfunction "VIN_4") (pintype "bidirectional"))
    )
    (net (code "39") (name "Net-(C5-+)") (class "Default")
      (node (ref "C5") (pin "1") (pinfunction "+_1") (pintype "passive"))
      (node (ref "L1") (pin "P$1") (pinfunction "P$1_P$1") (pintype "bidirectional"))
      (node (ref "U7") (pin "5") (pinfunction "PHASE_5") (pintype "bidirectional"))
    )
    (net (code "40") (name "Net-(C5--)") (class "Default")
      (node (ref "C5") (pin "2") (pinfunction "-_2") (pintype "passive"))
      (node (ref "U7") (pin "3") (pinfunction "BOOT_3") (pintype "bidirectional"))
    )
    (net (code "41") (name "Net-(C6-+)") (class "Default")
      (node (ref "C6") (pin "1") (pinfunction "+_1") (pintype "passive"))
      (node (ref "U7") (pin "1") (pinfunction "SS_1") (pintype "bidirectional"))
      (node (ref "U7") (pin "11") (pinfunction "COMP_11") (pintype "bidirectional"))
      (node (ref "U7") (pin "12") (pinfunction "FS_12") (pintype "bidirectional"))
      (node (ref "U7") (pin "9") (pinfunction "VCC_9") (pintype "bidirectional"))
    )
    (net (code "42") (name "Net-(C7--)") (class "Default")
      (node (ref "C7") (pin "2") (pinfunction "-_2") (pintype "passive"))
      (node (ref "R41") (pin "1") (pinfunction "1_1") (pintype "passive"))
      (node (ref "R43") (pin "2") (pinfunction "2_2") (pintype "passive"))
      (node (ref "U7") (pin "10") (pinfunction "FB_10") (pintype "bidirectional"))
    )
    (net (code "43") (name "Net-(C13--)") (class "Default")
      (node (ref "C13") (pin "2") (pinfunction "-_2") (pintype "passive"))
      (node (ref "C14") (pin "1") (pinfunction "+_1") (pintype "passive"))
      (node (ref "R19") (pin "2") (pinfunction "2_2") (pintype "passive"))
      (node (ref "U2") (pin "8") (pinfunction "C9_8") (pintype "bidirectional"))
    )
    (net (code "44") (name "Net-(C14--)") (class "Default")
      (node (ref "C14") (pin "2") (pinfunction "-_2") (pintype "passive"))
      (node (ref "C15") (pin "1") (pinfunction "+_1") (pintype "passive"))
      (node (ref "R23") (pin "1") (pinfunction "1_1") (pintype "passive"))
      (node (ref "U2") (pin "10") (pinfunction "C8_10") (pintype "bidirectional"))
    )
    (net (code "45") (name "Net-(C15--)") (class "Default")
      (node (ref "C15") (pin "2") (pinfunction "-_2") (pintype "passive"))
      (node (ref "C16") (pin "1") (pinfunction "+_1") (pintype "passive"))
      (node (ref "R24") (pin "1") (pinfunction "1_1") (pintype "passive"))
      (node (ref "R54") (pin "1") (pinfunction "1_1") (pintype "passive"))
      (node (ref "U2") (pin "12") (pinfunction "C7_12") (pintype "bidirectional"))
    )
    (net (code "46") (name "Net-(C16--)") (class "Default")
      (node (ref "C16") (pin "2") (pinfunction "-_2") (pintype "passive"))
      (node (ref "C17") (pin "1") (pinfunction "+_1") (pintype "passive"))
      (node (ref "R25") (pin "1") (pinfunction "1_1") (pintype "passive"))
      (node (ref "U2") (pin "18") (pinfunction "C4_18") (pintype "bidirectional"))
    )
    (net (code "47") (name "Net-(C17--)") (class "Default")
      (node (ref "C17") (pin "2") (pinfunction "-_2") (pintype "passive"))
      (node (ref "C18") (pin "1") (pinfunction "+_1") (pintype "passive"))
      (node (ref "R26") (pin "1") (pinfunction "1_1") (pintype "passive"))
      (node (ref "U2") (pin "20") (pinfunction "C3_20") (pintype "bidirectional"))
    )
    (net (code "48") (name "Net-(C18--)") (class "Default")
      (node (ref "C18") (pin "2") (pinfunction "-_2") (pintype "passive"))
      (node (ref "C19") (pin "1") (pinfunction "+_1") (pintype "passive"))
      (node (ref "R27") (pin "1") (pinfunction "1_1") (pintype "passive"))
      (node (ref "U2") (pin "22") (pinfunction "C2_22") (pintype "bidirectional"))
    )
    (net (code "49") (name "Net-(C19--)") (class "Default")
      (node (ref "C19") (pin "2") (pinfunction "-_2") (pintype "passive"))
      (node (ref "C20") (pin "1") (pinfunction "+_1") (pintype "passive"))
      (node (ref "R28") (pin "1") (pinfunction "1_1") (pintype "passive"))
      (node (ref "U2") (pin "24") (pinfunction "C1_24") (pintype "bidirectional"))
    )
    (net (code "50") (name "Net-(C21-+)") (class "Default")
      (node (ref "C21") (pin "1") (pinfunction "+_1") (pintype "passive"))
      (node (ref "U2") (pin "34") (pinfunction "VREF2_34") (pintype "bidirectional"))
    )
    (net (code "51") (name "Net-(C22-+)") (class "Default")
      (node (ref "C22") (pin "1") (pinfunction "+_1") (pintype "passive"))
      (node (ref "U2") (pin "35") (pinfunction "VREF1_35") (pintype "bidirectional"))
    )
    (net (code "52") (name "Net-(D1-PadC)") (class "Default")
      (node (ref "D1") (pin "C") (pinfunction "C_C") (pintype "passive"))
      (node (ref "R29") (pin "2") (pinfunction "2_2") (pintype "passive"))
    )
    (net (code "53") (name "Net-(D2-PadC)") (class "Default")
      (node (ref "D2") (pin "C") (pinfunction "C_C") (pintype "passive"))
      (node (ref "R30") (pin "2") (pinfunction "2_2") (pintype "passive"))
    )
    (net (code "54") (name "Net-(D3-PadC)") (class "Default")
      (node (ref "D3") (pin "C") (pinfunction "C_C") (pintype "passive"))
      (node (ref "R31") (pin "2") (pinfunction "2_2") (pintype "passive"))
    )
    (net (code "55") (name "Net-(D4-PadC)") (class "Default")
      (node (ref "D4") (pin "C") (pinfunction "C_C") (pintype "passive"))
      (node (ref "R32") (pin "2") (pinfunction "2_2") (pintype "passive"))
    )
    (net (code "56") (name "Net-(D5-PadC)") (class "Default")
      (node (ref "D5") (pin "C") (pinfunction "C_C") (pintype "passive"))
      (node (ref "R33") (pin "2") (pinfunction "2_2") (pintype "passive"))
    )
    (net (code "57") (name "Net-(D6-PadC)") (class "Default")
      (node (ref "D6") (pin "C") (pinfunction "C_C") (pintype "passive"))
      (node (ref "R34") (pin "2") (pinfunction "2_2") (pintype "passive"))
    )
    (net (code "58") (name "Net-(D7-PadC)") (class "Default")
      (node (ref "D7") (pin "C") (pinfunction "C_C") (pintype "passive"))
      (node (ref "R35") (pin "2") (pinfunction "2_2") (pintype "passive"))
    )
    (net (code "59") (name "Net-(D8-PadA)") (class "Default")
      (node (ref "D8") (pin "A") (pinfunction "A_A") (pintype "passive"))
      (node (ref "R1") (pin "1") (pinfunction "1_1") (pintype "passive"))
    )
    (net (code "60") (name "Net-(D9-PadA)") (class "Default")
      (node (ref "D9") (pin "A") (pinfunction "A_A") (pintype "passive"))
      (node (ref "R2") (pin "1") (pinfunction "1_1") (pintype "passive"))
    )
    (net (code "61") (name "Net-(D10-A)") (class "Default")
      (node (ref "D10") (pin "P$2") (pinfunction "A_P$2") (pintype "bidirectional"))
      (node (ref "R40") (pin "2") (pinfunction "2_2") (pintype "passive"))
      (node (ref "R44") (pin "1") (pinfunction "1_1") (pintype "passive"))
    )
    (net (code "62") (name "Net-(D10-C)") (class "Default")
      (node (ref "D10") (pin "P$1") (pinfunction "C_P$1") (pintype "bidirectional"))
      (node (ref "R39") (pin "1") (pinfunction "1_1") (pintype "passive"))
    )
    (net (code "63") (name "Net-(D11-PadA)") (class "Default")
      (node (ref "D11") (pin "A") (pinfunction "A_A") (pintype "passive"))
      (node (ref "R36") (pin "1") (pinfunction "1_1") (pintype "passive"))
    )
    (net (code "64") (name "Net-(K1-PadNO)") (class "Default")
      (node (ref "K1") (pin "NO") (pinfunction "NO_NO") (pintype "bidirectional"))
      (node (ref "U3") (pin "3") (pinfunction "IP-_3") (pintype "bidirectional"))
      (node (ref "U3") (pin "4") (pinfunction "IP-_4") (pintype "bidirectional"))
    )
    (net (code "65") (name "Net-(K1A-+1)") (class "Default")
      (node (ref "K1") (pin "-8-S") (pinfunction "+1_-8-S") (pintype "passive"))
      (node (ref "U6") (pin "6") (pinfunction "D_6") (pintype "passive"))
    )
    (net (code "66") (name "Net-(K1A-+2)") (class "Default")
      (node (ref "K1") (pin "-9-R") (pinfunction "+2_-9-R") (pintype "passive"))
      (node (ref "U6") (pin "3") (pinfunction "D_3") (pintype "passive"))
    )
    (net (code "67") (name "Net-(Q2-P$1)") (class "Default")
      (node (ref "Q2") (pin "1") (pinfunction "P$1_1") (pintype "input"))
      (node (ref "R44") (pin "2") (pinfunction "2_2") (pintype "passive"))
    )
    (net (code "68") (name "Net-(Q2-P$2)") (class "Default")
      (node (ref "Q2") (pin "2") (pinfunction "P$2_2") (pintype "output"))
      (node (ref "R42") (pin "2") (pinfunction "2_2") (pintype "passive"))
      (node (ref "U7") (pin "7") (pinfunction "EN_7") (pintype "bidirectional"))
    )
    (net (code "69") (name "Net-(QB1-D)") (class "Default")
      (node (ref "D1") (pin "A") (pinfunction "A_A") (pintype "passive"))
      (node (ref "QB1") (pin "2") (pinfunction "D_2") (pintype "passive"))
      (node (ref "R14") (pin "P$2") (pinfunction "2_P$2") (pintype "passive"))
    )
    (net (code "70") (name "Net-(QB1-G)") (class "Default")
      (node (ref "QB1") (pin "1") (pinfunction "G_1") (pintype "passive"))
      (node (ref "R5") (pin "1") (pinfunction "1_1") (pintype "passive"))
    )
    (net (code "71") (name "Net-(QB1-S)") (class "Default")
      (node (ref "J9") (pin "8") (pinfunction "8_8") (pintype "passive"))
      (node (ref "QB1") (pin "3") (pinfunction "S_3") (pintype "passive"))
      (node (ref "R18") (pin "2") (pinfunction "2_2") (pintype "passive"))
      (node (ref "R19") (pin "1") (pinfunction "1_1") (pintype "passive"))
    )
    (net (code "72") (name "Net-(QB2-D)") (class "Default")
      (node (ref "D2") (pin "A") (pinfunction "A_A") (pintype "passive"))
      (node (ref "QB2") (pin "2") (pinfunction "D_2") (pintype "passive"))
      (node (ref "R15") (pin "P$2") (pinfunction "2_P$2") (pintype "passive"))
    )
    (net (code "73") (name "Net-(QB2-G)") (class "Default")
      (node (ref "QB2") (pin "1") (pinfunction "G_1") (pintype "passive"))
      (node (ref "R6") (pin "1") (pinfunction "1_1") (pintype "passive"))
    )
    (net (code "74") (name "Net-(QB2-S)") (class "Default")
      (node (ref "J9") (pin "7") (pinfunction "7_7") (pintype "passive"))
      (node (ref "QB2") (pin "3") (pinfunction "S_3") (pintype "passive"))
      (node (ref "R14") (pin "P$1") (pinfunction "1_P$1") (pintype "passive"))
      (node (ref "R23") (pin "2") (pinfunction "2_2") (pintype "passive"))
      (node (ref "R29") (pin "1") (pinfunction "1_1") (pintype "passive"))
    )
    (net (code "75") (name "Net-(QB3-D)") (class "Default")
      (node (ref "D3") (pin "A") (pinfunction "A_A") (pintype "passive"))
      (node (ref "QB3") (pin "2") (pinfunction "D_2") (pintype "passive"))
      (node (ref "R16") (pin "P$2") (pinfunction "2_P$2") (pintype "passive"))
    )
    (net (code "76") (name "Net-(QB3-G)") (class "Default")
      (node (ref "QB3") (pin "1") (pinfunction "G_1") (pintype "passive"))
      (node (ref "R7") (pin "1") (pinfunction "1_1") (pintype "passive"))
    )
    (net (code "77") (name "Net-(QB3-S)") (class "Default")
      (node (ref "J9") (pin "6") (pinfunction "6_6") (pintype "passive"))
      (node (ref "QB3") (pin "3") (pinfunction "S_3") (pintype "passive"))
      (node (ref "R15") (pin "P$1") (pinfunction "1_P$1") (pintype "passive"))
      (node (ref "R24") (pin "2") (pinfunction "2_2") (pintype "passive"))
      (node (ref "R30") (pin "1") (pinfunction "1_1") (pintype "passive"))
    )
    (net (code "78") (name "Net-(QB4-D)") (class "Default")
      (node (ref "D4") (pin "A") (pinfunction "A_A") (pintype "passive"))
      (node (ref "QB4") (pin "2") (pinfunction "D_2") (pintype "passive"))
      (node (ref "R17") (pin "P$2") (pinfunction "2_P$2") (pintype "passive"))
    )
    (net (code "79") (name "Net-(QB4-G)") (class "Default")
      (node (ref "QB4") (pin "1") (pinfunction "G_1") (pintype "passive"))
      (node (ref "R8") (pin "1") (pinfunction "1_1") (pintype "passive"))
    )
    (net (code "80") (name "Net-(QB4-S)") (class "Default")
      (node (ref "J9") (pin "5") (pinfunction "5_5") (pintype "passive"))
      (node (ref "QB4") (pin "3") (pinfunction "S_3") (pintype "passive"))
      (node (ref "R16") (pin "P$1") (pinfunction "1_P$1") (pintype "passive"))
      (node (ref "R25") (pin "2") (pinfunction "2_2") (pintype "passive"))
      (node (ref "R31") (pin "1") (pinfunction "1_1") (pintype "passive"))
    )
    (net (code "81") (name "Net-(QB5-D)") (class "Default")
      (node (ref "D5") (pin "A") (pinfunction "A_A") (pintype "passive"))
      (node (ref "QB5") (pin "2") (pinfunction "D_2") (pintype "passive"))
      (node (ref "R20") (pin "P$2") (pinfunction "2_P$2") (pintype "passive"))
    )
    (net (code "82") (name "Net-(QB5-G)") (class "Default")
      (node (ref "QB5") (pin "1") (pinfunction "G_1") (pintype "passive"))
      (node (ref "R9") (pin "1") (pinfunction "1_1") (pintype "passive"))
    )
    (net (code "83") (name "Net-(QB5-S)") (class "Default")
      (node (ref "J9") (pin "4") (pinfunction "4_4") (pintype "passive"))
      (node (ref "QB5") (pin "3") (pinfunction "S_3") (pintype "passive"))
      (node (ref "R17") (pin "P$1") (pinfunction "1_P$1") (pintype "passive"))
      (node (ref "R26") (pin "2") (pinfunction "2_2") (pintype "passive"))
      (node (ref "R32") (pin "1") (pinfunction "1_1") (pintype "passive"))
    )
    (net (code "84") (name "Net-(QB6-D)") (class "Default")
      (node (ref "D6") (pin "A") (pinfunction "A_A") (pintype "passive"))
      (node (ref "QB6") (pin "2") (pinfunction "D_2") (pintype "passive"))
      (node (ref "R21") (pin "P$2") (pinfunction "2_P$2") (pintype "passive"))
    )
    (net (code "85") (name "Net-(QB6-G)") (class "Default")
      (node (ref "QB6") (pin "1") (pinfunction "G_1") (pintype "passive"))
      (node (ref "R10") (pin "1") (pinfunction "1_1") (pintype "passive"))
    )
    (net (code "86") (name "Net-(QB6-S)") (class "Default")
      (node (ref "J9") (pin "3") (pinfunction "3_3") (pintype "passive"))
      (node (ref "QB6") (pin "3") (pinfunction "S_3") (pintype "passive"))
      (node (ref "R20") (pin "P$1") (pinfunction "1_P$1") (pintype "passive"))
      (node (ref "R27") (pin "2") (pinfunction "2_2") (pintype "passive"))
      (node (ref "R33") (pin "1") (pinfunction "1_1") (pintype "passive"))
    )
    (net (code "87") (name "Net-(QB7-D)") (class "Default")
      (node (ref "D7") (pin "A") (pinfunction "A_A") (pintype "passive"))
      (node (ref "QB7") (pin "2") (pinfunction "D_2") (pintype "passive"))
      (node (ref "R22") (pin "P$2") (pinfunction "2_P$2") (pintype "passive"))
    )
    (net (code "88") (name "Net-(QB7-G)") (class "Default")
      (node (ref "QB7") (pin "1") (pinfunction "G_1") (pintype "passive"))
      (node (ref "R11") (pin "1") (pinfunction "1_1") (pintype "passive"))
    )
    (net (code "89") (name "Net-(QB7-S)") (class "Default")
      (node (ref "J9") (pin "2") (pinfunction "2_2") (pintype "passive"))
      (node (ref "QB7") (pin "3") (pinfunction "S_3") (pintype "passive"))
      (node (ref "R21") (pin "P$1") (pinfunction "1_P$1") (pintype "passive"))
      (node (ref "R28") (pin "2") (pinfunction "2_2") (pintype "passive"))
      (node (ref "R34") (pin "1") (pinfunction "1_1") (pintype "passive"))
    )
    (net (code "90") (name "Net-(R12A-2)") (class "Default")
      (node (ref "R12") (pin "5") (pinfunction "2_5") (pintype "passive"))
      (node (ref "R12") (pin "6") (pinfunction "2_6") (pintype "passive"))
      (node (ref "R12") (pin "7") (pinfunction "2_7") (pintype "passive"))
      (node (ref "R12") (pin "8") (pinfunction "2_8") (pintype "passive"))
      (node (ref "R13") (pin "6") (pinfunction "2_6") (pintype "passive"))
      (node (ref "R13") (pin "7") (pinfunction "2_7") (pintype "passive"))
      (node (ref "R13") (pin "8") (pinfunction "2_8") (pintype "passive"))
      (node (ref "U8") (pin "2") (pinfunction "D_2") (pintype "passive"))
    )
    (net (code "91") (name "Net-(U1-PGC{slash}RB6)") (class "Default")
      (node (ref "J1") (pin "5") (pinfunction "5_5") (pintype "passive"))
      (node (ref "U1") (pin "16") (pinfunction "PGC/RB6_16") (pintype "bidirectional"))
    )
    (net (code "92") (name "Net-(U1-PGD{slash}RB7)") (class "Default")
      (node (ref "J1") (pin "4") (pinfunction "4_4") (pintype "passive"))
      (node (ref "U1") (pin "17") (pinfunction "PGD/RB7_17") (pintype "bidirectional"))
    )
    (net (code "93") (name "Net-(U1-RA7)") (class "Default")
      (node (ref "R36") (pin "2") (pinfunction "2_2") (pintype "passive"))
      (node (ref "U1") (pin "30") (pinfunction "RA7_30") (pintype "bidirectional"))
    )
    (net (code "94") (name "Net-(U1-RD6)") (class "Default")
      (node (ref "R56") (pin "2") (pinfunction "2_2") (pintype "passive"))
      (node (ref "U1") (pin "4") (pinfunction "RD6_4") (pintype "bidirectional"))
    )
    (net (code "95") (name "Net-(U1-RD7)") (class "Default")
      (node (ref "R55") (pin "2") (pinfunction "2_2") (pintype "passive"))
      (node (ref "U1") (pin "5") (pinfunction "RD7_5") (pintype "bidirectional"))
    )
    (net (code "96") (name "Net-(U1-~{MCLR})") (class "Default")
      (node (ref "J1") (pin "1") (pinfunction "1_1") (pintype "passive"))
      (node (ref "R4") (pin "1") (pinfunction "1_1") (pintype "passive"))
      (node (ref "U1") (pin "18") (pinfunction "~{MCLR}_18") (pintype "bidirectional"))
    )
    (net (code "97") (name "Net-(U2-C5)") (class "Default")
      (node (ref "R54") (pin "2") (pinfunction "2_2") (pintype "passive"))
      (node (ref "U2") (pin "14") (pinfunction "C6_14") (pintype "bidirectional"))
      (node (ref "U2") (pin "16") (pinfunction "C5_16") (pintype "bidirectional"))
    )
    (net (code "98") (name "Net-(U2-SWTEN)") (class "Default")
      (node (ref "R47") (pin "1") (pinfunction "1_1") (pintype "passive"))
      (node (ref "U2") (pin "36") (pinfunction "SWTEN_36") (pintype "bidirectional"))
    )
    (net (code "99") (name "Net-(U4-A)") (class "Default")
      (node (ref "J6") (pin "4") (pinfunction "4_4") (pintype "passive"))
      (node (ref "R3") (pin "1") (pinfunction "1_1") (pintype "passive"))
      (node (ref "U4") (pin "6") (pinfunction "A_6") (pintype "bidirectional"))
    )
    (net (code "100") (name "Net-(U4-B)") (class "Default")
      (node (ref "J6") (pin "1") (pinfunction "1_1") (pintype "passive"))
      (node (ref "R3") (pin "2") (pinfunction "2_2") (pintype "passive"))
      (node (ref "U4") (pin "7") (pinfunction "B_7") (pintype "bidirectional"))
    )
    (net (code "101") (name "Net-(U8-G)") (class "Default")
      (node (ref "R45") (pin "1") (pinfunction "1_1") (pintype "passive"))
      (node (ref "R46") (pin "1") (pinfunction "1_1") (pintype "passive"))
      (node (ref "U8") (pin "1") (pinfunction "G_1") (pintype "passive"))
    )
    (net (code "102") (name "unconnected-(K1-PadNC)") (class "Default")
      (node (ref "K1") (pin "NC") (pinfunction "NC_NC") (pintype "bidirectional"))
    )
    (net (code "103") (name "unconnected-(R13D-1-Pad4)") (class "Default")
      (node (ref "R13") (pin "4") (pinfunction "1_4") (pintype "passive"))
    )
    (net (code "104") (name "unconnected-(R13D-2-Pad5)") (class "Default")
      (node (ref "R13") (pin "5") (pinfunction "2_5") (pintype "passive"))
    )
    (net (code "105") (name "unconnected-(U1-RA4-Pad23)") (class "Default")
      (node (ref "U1") (pin "23") (pinfunction "RA4_23") (pintype "bidirectional"))
    )
    (net (code "106") (name "unconnected-(U1-RA6-Pad31)") (class "Default")
      (node (ref "U1") (pin "31") (pinfunction "RA6_31") (pintype "bidirectional"))
    )
    (net (code "107") (name "unconnected-(U1-RB0-Pad8)") (class "Default")
      (node (ref "U1") (pin "8") (pinfunction "RB0_8") (pintype "bidirectional"))
    )
    (net (code "108") (name "unconnected-(U1-RB1-Pad9)") (class "Default")
      (node (ref "U1") (pin "9") (pinfunction "RB1_9") (pintype "bidirectional"))
    )
    (net (code "109") (name "unconnected-(U1-RB2-Pad10)") (class "Default")
      (node (ref "U1") (pin "10") (pinfunction "RB2_10") (pintype "bidirectional"))
    )
    (net (code "110") (name "unconnected-(U1-RB5-Pad15)") (class "Default")
      (node (ref "U1") (pin "15") (pinfunction "RB5_15") (pintype "bidirectional"))
    )
    (net (code "111") (name "unconnected-(U1-RC0-Pad32)") (class "Default")
      (node (ref "U1") (pin "32") (pinfunction "RC0_32") (pintype "bidirectional"))
    )
    (net (code "112") (name "unconnected-(U1-RC1-Pad35)") (class "Default")
      (node (ref "U1") (pin "35") (pinfunction "RC1_35") (pintype "bidirectional"))
    )
    (net (code "113") (name "unconnected-(U1-RC2-Pad36)") (class "Default")
      (node (ref "U1") (pin "36") (pinfunction "RC2_36") (pintype "bidirectional"))
    )
    (net (code "114") (name "unconnected-(U1-RC3-Pad37)") (class "Default")
      (node (ref "U1") (pin "37") (pinfunction "RC3_37") (pintype "bidirectional"))
    )
    (net (code "115") (name "unconnected-(U1-RC4-Pad42)") (class "Default")
      (node (ref "U1") (pin "42") (pinfunction "RC4_42") (pintype "bidirectional"))
    )
    (net (code "116") (name "unconnected-(U1-RD2-Pad40)") (class "Default")
      (node (ref "U1") (pin "40") (pinfunction "RD2_40") (pintype "bidirectional"))
    )
    (net (code "117") (name "unconnected-(U1-RD5-Pad3)") (class "Default")
      (node (ref "U1") (pin "3") (pinfunction "RD5_3") (pintype "bidirectional"))
    )
    (net (code "118") (name "unconnected-(U2-DRIVE-Pad38)") (class "Default")
      (node (ref "U2") (pin "38") (pinfunction "DRIVE_38") (pintype "bidirectional"))
    )
    (net (code "119") (name "unconnected-(U2-S5-Pad17)") (class "Default")
      (node (ref "U2") (pin "17") (pinfunction "S5_17") (pintype "bidirectional"))
    )
    (net (code "120") (name "unconnected-(U2-S6-Pad15)") (class "Default")
      (node (ref "U2") (pin "15") (pinfunction "S6_15") (pintype "bidirectional"))
    )
    (net (code "121") (name "unconnected-(U2-S10-Pad7)") (class "Default")
      (node (ref "U2") (pin "7") (pinfunction "S10_7") (pintype "bidirectional"))
    )
    (net (code "122") (name "unconnected-(U2-S11-Pad5)") (class "Default")
      (node (ref "U2") (pin "5") (pinfunction "S11_5") (pintype "bidirectional"))
    )
    (net (code "123") (name "unconnected-(U2-S12-Pad3)") (class "Default")
      (node (ref "U2") (pin "3") (pinfunction "S12_3") (pintype "bidirectional"))
    )
    (net (code "124") (name "unconnected-(U2-WDT-Pad39)") (class "Default")
      (node (ref "U2") (pin "39") (pinfunction "WDT_39") (pintype "bidirectional"))
    )
    (net (code "125") (name "unconnected-(U4-GND-Pad5)") (class "Default")
      (node (ref "U4") (pin "5") (pinfunction "GND_5") (pintype "bidirectional"))
    )
    (net (code "126") (name "unconnected-(U7-PG-Pad8)") (class "Default")
      (node (ref "U7") (pin "8") (pinfunction "PG_8") (pintype "bidirectional"))
    )
  )
)
